# TIDA-010967_QSPI_Flash.net
KiCad netlist of a schematic drawn in Altium Designer
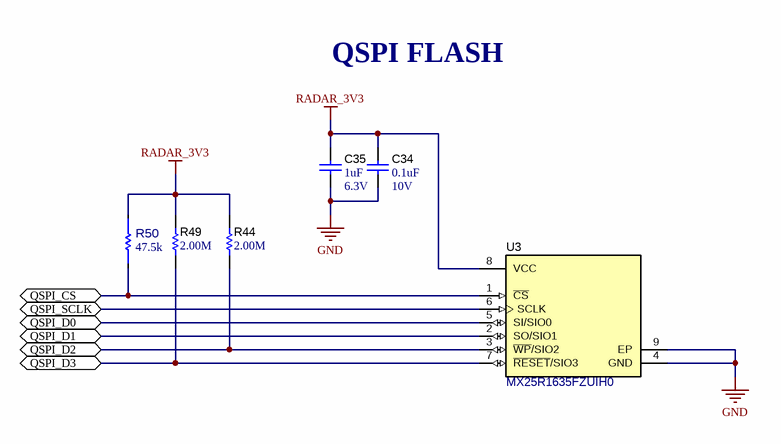
[diagram p0: TIDA-010967_QSPI_Flash.SchDoc]

(export (version "E")
  (design (tool "Eeschema 10.0.6"))
  (components
    (comp (ref "C34")
      (value "GRM033C71A104KE14D")
      (footprint "0201")
      (description "CAP, CERM, 0.1 uF, 10 V,+/- 10%, X7S, 0201")
      (fields
        (field (name "MANUFACTURER") "MuRata")
        (field (name "VALUE2") "10V")
        (field (name "VALUEDISPLAYED") "0.1uF")
        (field (name "PUBLISHER") "Texas Instruments")
      )
      (libsource (lib "Altium Vault - TI") (part "Capacitor"))
    )
    (comp (ref "C35")
      (value "GRM155R70J105KA12D")
      (footprint "0402L")
      (description "CAP, CERM, 1 uF, 6.3 V,+/- 10%, X7R, 0402")
      (fields
        (field (name "MANUFACTURER") "MuRata")
        (field (name "VDC_V") "6.3V")
        (field (name "VALUEDISPLAYED") "1uF")
        (field (name "PUBLISHER") "Texas Instruments")
      )
      (libsource (lib "Altium Vault - TI") (part "Capacitor"))
    )
    (comp (ref "R44")
      (value "CRCW04022M00FKED")
      (footprint "0402")
      (description "RES, 2.00 M, 1%, 0.063 W, AEC-Q200 Grade 0, 0402")
      (fields (field (name "MANUFACTURER") "Vishay-Dale") (field (name "VALUEDISPLAYED") "2.00M"))
      (libsource (lib "Altium Vault - TI") (part "Resistor"))
    )
    (comp (ref "R49")
      (value "CRCW04022M00FKED")
      (footprint "0402")
      (description "RES, 2.00 M, 1%, 0.063 W, AEC-Q200 Grade 0, 0402")
      (fields (field (name "MANUFACTURER") "Vishay-Dale") (field (name "VALUEDISPLAYED") "2.00M"))
      (libsource (lib "Altium Vault - TI") (part "Resistor"))
    )
    (comp (ref "R50")
      (value "AC0402FR-0747K5L")
      (footprint "FP-AC0402FR-0747K5L_0402-MFG")
      (description "Res Thick Film 0402 47.5K Ohm 1% 1/16W ±100ppm/°C Molded SMD Paper T/R")
      (fields
        (field (name "DIGIKEY PART NUMBER") "13-AC0402FR-0747K5LCT-ND")
        (field (name "RES_OHM") "47.5k")
        (field (name "MOUSER PART NUMBER") "603-AC0402FR-0747K5L")
      )
      (libsource (lib "Altium Vault - TI") (part "SYM-AC0402FR-0747K5L"))
    )
    (comp (ref "U3")
      (value "MX25R1635FZUIH0")
      (footprint "USON-8L")
      (description "ULTRA LOW POWER, 16M-BIT [x 1/x 2/x 4] CMOS MXSMIO (SERIAL MULTI I/O) FLASH MEMORY, SON-8")
      (fields (field (name "MANUFACTURER") "Macronix International Co., LTD"))
      (libsource (lib "Altium Vault - TI") (part "MX25R1635FZNIH"))
    )
  )
  (nets
    (net (code "1") (name "/QSPI_CS") (class "Default")
      (node (ref "R50") (pin "2") (pinfunction "2_2") (pintype "passive"))
      (node (ref "U3") (pin "1") (pinfunction "CS_1") (pintype "input"))
    )
    (net (code "2") (name "/QSPI_D0") (class "Default")
      (node (ref "U3") (pin "5") (pinfunction "SI/SIO0_5") (pintype "bidirectional"))
    )
    (net (code "3") (name "/QSPI_D1") (class "Default")
      (node (ref "U3") (pin "2") (pinfunction "SO/SIO1_2") (pintype "bidirectional"))
    )
    (net (code "4") (name "/QSPI_D2") (class "Default")
      (node (ref "R44") (pin "1") (pinfunction "1_1") (pintype "passive"))
      (node (ref "U3") (pin "3") (pinfunction "~{WP}/SIO2_3") (pintype "bidirectional"))
    )
    (net (code "5") (name "/QSPI_D3") (class "Default")
      (node (ref "R49") (pin "1") (pinfunction "1_1") (pintype "passive"))
      (node (ref "U3") (pin "7") (pinfunction "~{RESET}/SIO3_7") (pintype "bidirectional"))
    )
    (net (code "6") (name "/QSPI_SCLK") (class "Default")
      (node (ref "U3") (pin "6") (pinfunction "SCLK_6") (pintype "input"))
    )
    (net (code "7") (name "GND") (class "Default")
      (node (ref "C34") (pin "1") (pinfunction "1_1") (pintype "passive"))
      (node (ref "C35") (pin "2") (pinfunction "2_2") (pintype "passive"))
      (node (ref "U3") (pin "4") (pinfunction "GND_4") (pintype "power_in"))
      (node (ref "U3") (pin "9") (pinfunction "EP_9") (pintype "passive"))
    )
    (net (code "8") (name "RADAR_3V3") (class "Default")
      (node (ref "C34") (pin "2") (pinfunction "2_2") (pintype "passive"))
      (node (ref "C35") (pin "1") (pinfunction "1_1") (pintype "passive"))
      (node (ref "R44") (pin "2") (pinfunction "2_2") (pintype "passive"))
      (node (ref "R49") (pin "2") (pinfunction "2_2") (pintype "passive"))
      (node (ref "R50") (pin "1") (pinfunction "1_1") (pintype "passive"))
      (node (ref "U3") (pin "8") (pinfunction "VCC_8") (pintype "power_in"))
    )
  )
)
